# arm_project_files.net
KiCad netlist of a schematic drawn in EasyEDA Pro
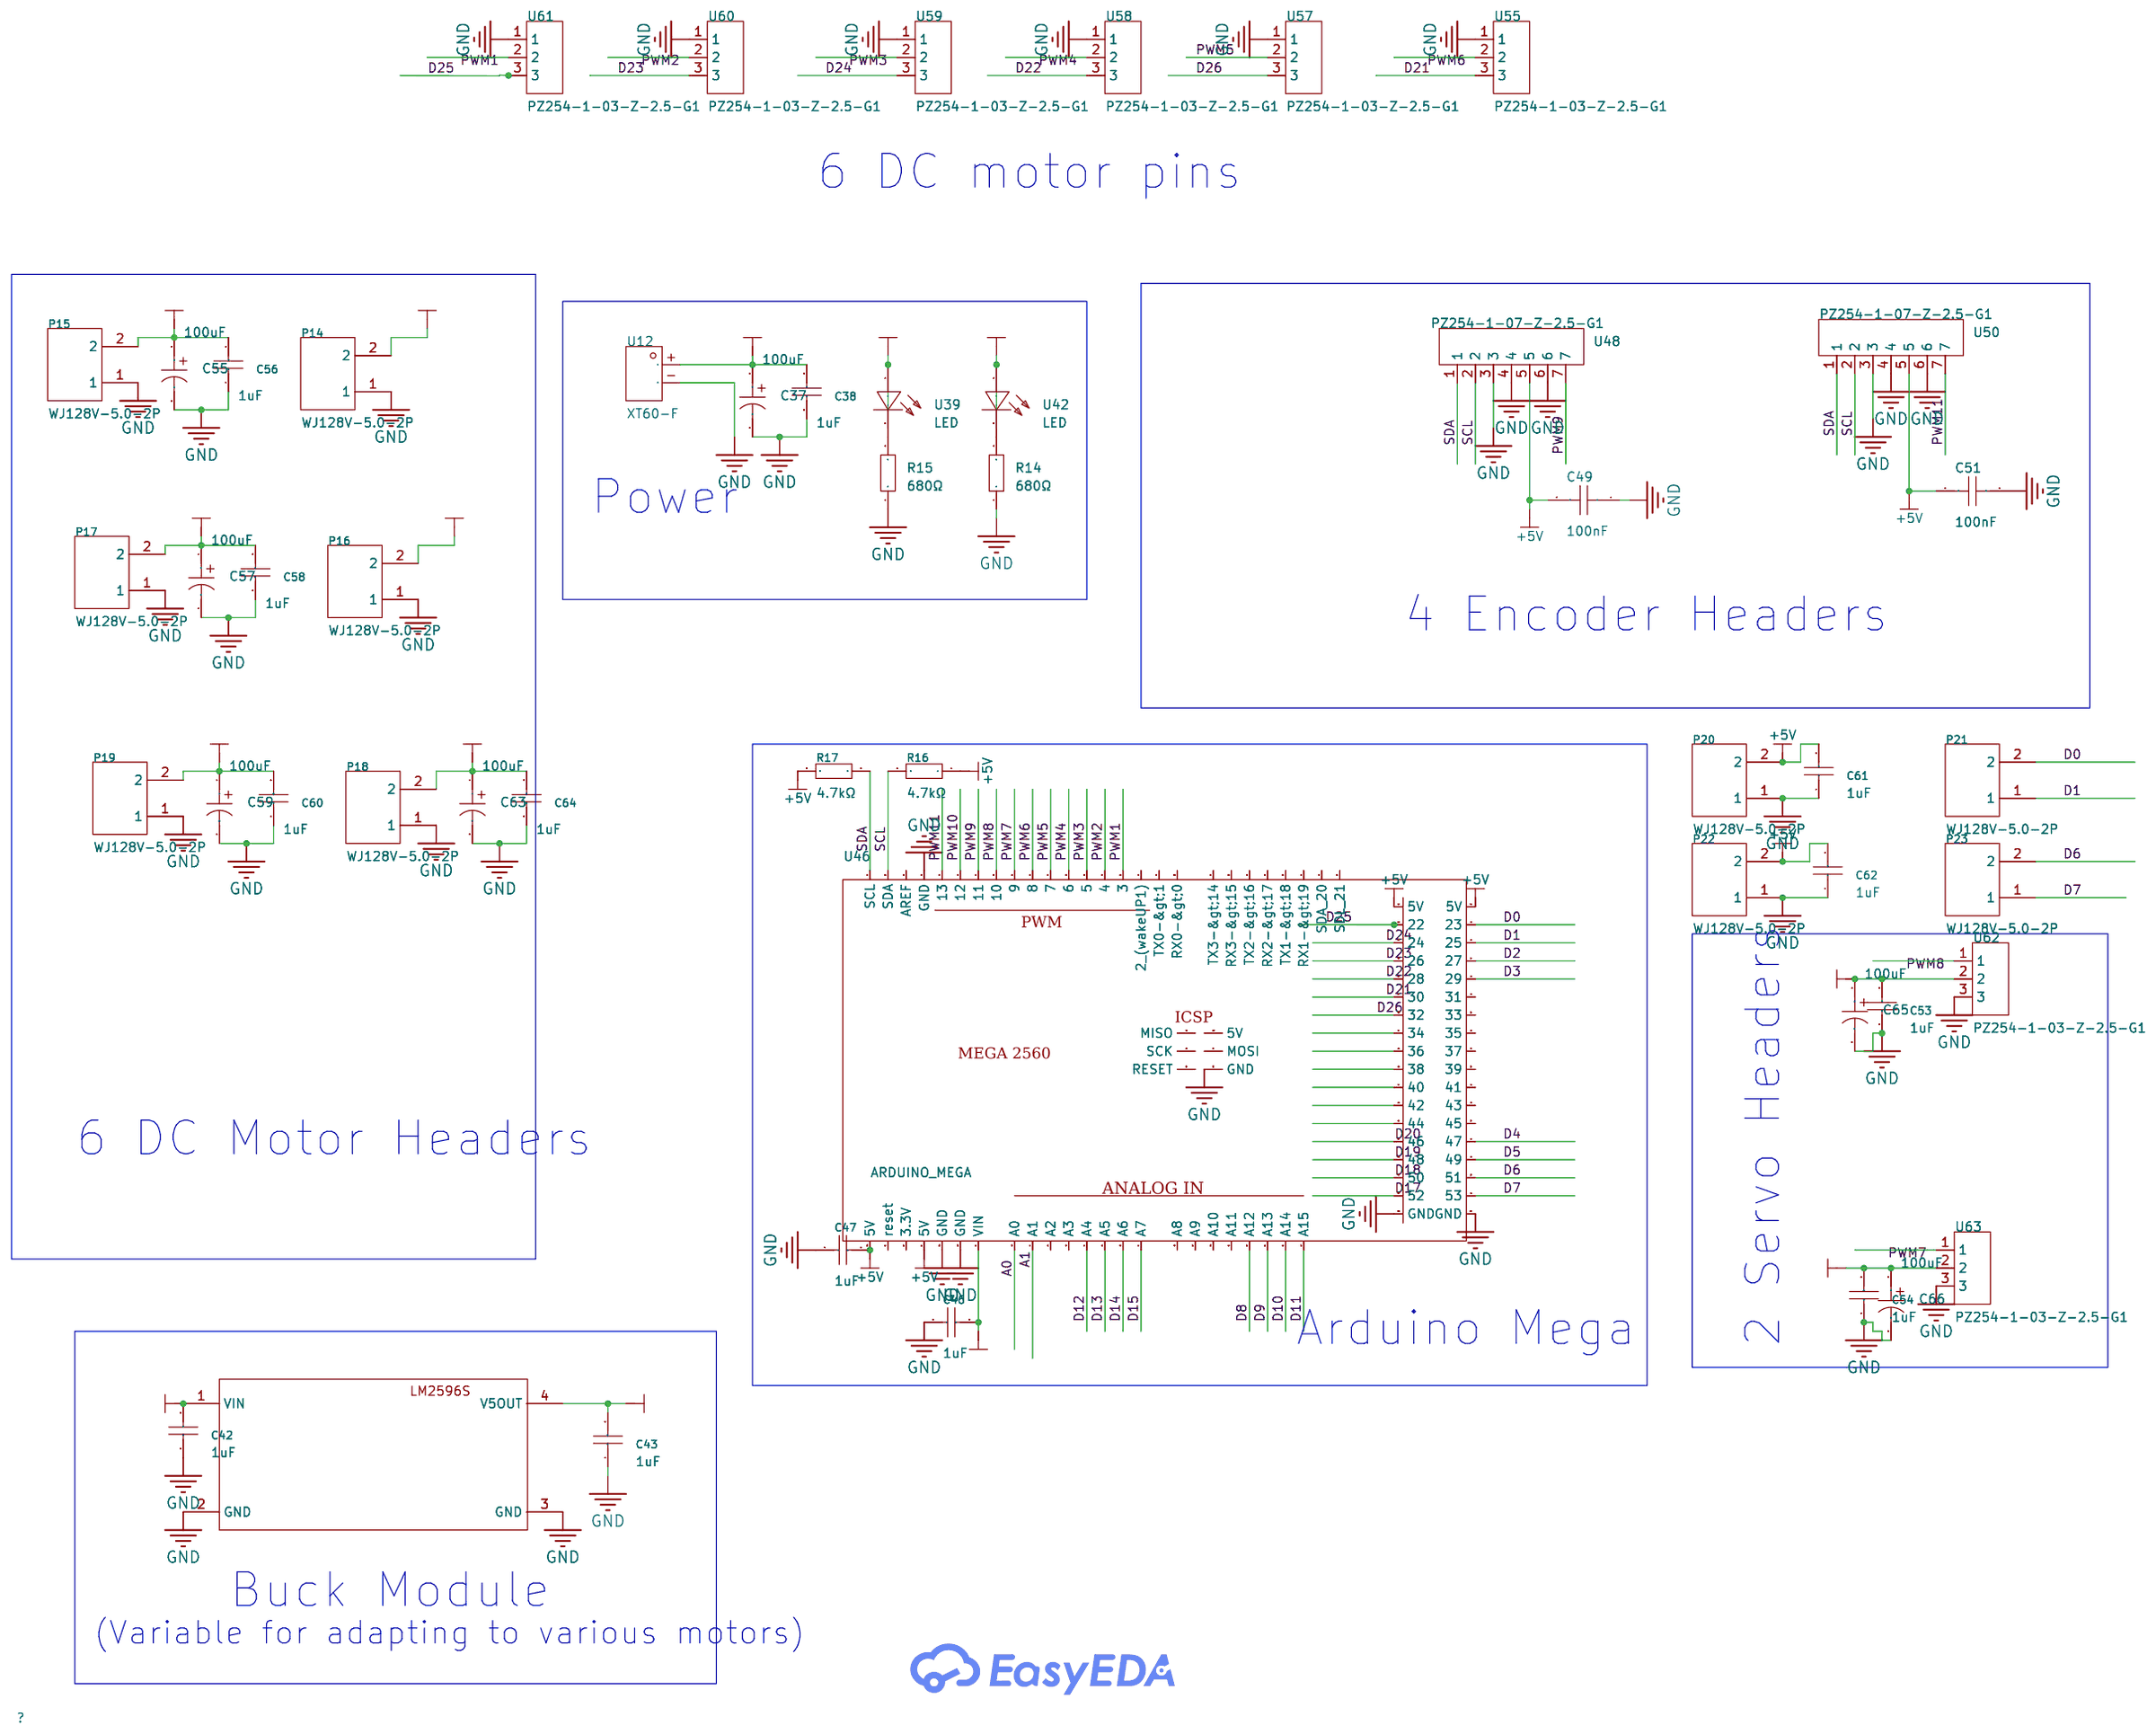
[diagram p0: schematic sheet]

(export (version "E")
  (design (tool "Eeschema 10.0.6"))
  (components
    (comp (ref "C37")
      (value "100uF")
      (footprint "easyedapro:CAP-TH_BD10.0-P5.00-D0.6-FD")
      (fields (field (name "Manufacturer Part") "100V100uF CD288") (field (name "Manufacturer") "HRK(鸿瑞凯电子)"))
      (libsource (lib "easyedapro") (part "100V100UF CD288"))
    )
    (comp (ref "C38")
      (value "1uF")
      (footprint "easyedapro:C0805")
      (fields
        (field (name "Manufacturer Part") "CC0805KKX7R8BB105")
        (field (name "Manufacturer") "YAGEO(国巨)")
      )
      (libsource (lib "easyedapro") (part "CC0805KKX7R8BB105"))
    )
    (comp (ref "C42")
      (value "1uF")
      (footprint "easyedapro:C0805")
      (fields
        (field (name "Manufacturer Part") "CC0805KKX7R8BB105")
        (field (name "Manufacturer") "YAGEO(国巨)")
      )
      (libsource (lib "easyedapro") (part "CC0805KKX7R8BB105"))
    )
    (comp (ref "C43")
      (value "1uF")
      (footprint "easyedapro:C0805")
      (fields
        (field (name "Manufacturer Part") "CC0805KKX7R8BB105")
        (field (name "Manufacturer") "YAGEO(国巨)")
      )
      (libsource (lib "easyedapro") (part "CC0805KKX7R8BB105"))
    )
    (comp (ref "C46")
      (value "1uF")
      (footprint "easyedapro:C0805")
      (fields
        (field (name "Manufacturer Part") "CC0805KKX7R8BB105")
        (field (name "Manufacturer") "YAGEO(国巨)")
      )
      (libsource (lib "easyedapro") (part "CC0805KKX7R8BB105"))
    )
    (comp (ref "C47")
      (value "1uF")
      (footprint "easyedapro:C0805")
      (fields
        (field (name "Manufacturer Part") "CC0805KKX7R8BB105")
        (field (name "Manufacturer") "YAGEO(国巨)")
      )
      (libsource (lib "easyedapro") (part "CC0805KKX7R8BB105"))
    )
    (comp (ref "C49")
      (value "100nF")
      (footprint "easyedapro:C0805")
      (description "Capacitance:100nF Tolerance:±10% Tolerance:±10% Voltage Rating:100V Temperature Coefficient:X7R")
      (fields (field (name "Manufacturer Part") "C0805X104K101T") (field (name "Manufacturer") "IHHEC(禾伸堂)"))
      (libsource (lib "easyedapro") (part "C0805X104K101T_C485772"))
    )
    (comp (ref "C51")
      (value "100nF")
      (footprint "easyedapro:C0805")
      (description "Capacitance:100nF Tolerance:±10% Tolerance:±10% Voltage Rating:100V Temperature Coefficient:X7R")
      (fields (field (name "Manufacturer Part") "C0805X104K101T") (field (name "Manufacturer") "IHHEC(禾伸堂)"))
      (libsource (lib "easyedapro") (part "C0805X104K101T_C485772"))
    )
    (comp (ref "C53")
      (value "1uF")
      (footprint "easyedapro:C0805")
      (fields
        (field (name "Manufacturer Part") "CC0805KKX7R8BB105")
        (field (name "Manufacturer") "YAGEO(国巨)")
      )
      (libsource (lib "easyedapro") (part "CC0805KKX7R8BB105"))
    )
    (comp (ref "C54")
      (value "1uF")
      (footprint "easyedapro:C0805")
      (fields
        (field (name "Manufacturer Part") "CC0805KKX7R8BB105")
        (field (name "Manufacturer") "YAGEO(国巨)")
      )
      (libsource (lib "easyedapro") (part "CC0805KKX7R8BB105"))
    )
    (comp (ref "C55")
      (value "100uF")
      (footprint "easyedapro:CAP-TH_BD10.0-P5.00-D0.6-FD")
      (fields (field (name "Manufacturer Part") "100V100uF CD288") (field (name "Manufacturer") "HRK(鸿瑞凯电子)"))
      (libsource (lib "easyedapro") (part "100V100UF CD288"))
    )
    (comp (ref "C56")
      (value "1uF")
      (footprint "easyedapro:C0805")
      (fields
        (field (name "Manufacturer Part") "CC0805KKX7R8BB105")
        (field (name "Manufacturer") "YAGEO(国巨)")
      )
      (libsource (lib "easyedapro") (part "CC0805KKX7R8BB105"))
    )
    (comp (ref "C57")
      (value "100uF")
      (footprint "easyedapro:CAP-TH_BD10.0-P5.00-D0.6-FD")
      (fields (field (name "Manufacturer Part") "100V100uF CD288") (field (name "Manufacturer") "HRK(鸿瑞凯电子)"))
      (libsource (lib "easyedapro") (part "100V100UF CD288"))
    )
    (comp (ref "C58")
      (value "1uF")
      (footprint "easyedapro:C0805")
      (fields
        (field (name "Manufacturer Part") "CC0805KKX7R8BB105")
        (field (name "Manufacturer") "YAGEO(国巨)")
      )
      (libsource (lib "easyedapro") (part "CC0805KKX7R8BB105"))
    )
    (comp (ref "C59")
      (value "100uF")
      (footprint "easyedapro:CAP-TH_BD10.0-P5.00-D0.6-FD")
      (fields (field (name "Manufacturer Part") "100V100uF CD288") (field (name "Manufacturer") "HRK(鸿瑞凯电子)"))
      (libsource (lib "easyedapro") (part "100V100UF CD288"))
    )
    (comp (ref "C60")
      (value "1uF")
      (footprint "easyedapro:C0805")
      (fields
        (field (name "Manufacturer Part") "CC0805KKX7R8BB105")
        (field (name "Manufacturer") "YAGEO(国巨)")
      )
      (libsource (lib "easyedapro") (part "CC0805KKX7R8BB105"))
    )
    (comp (ref "C61")
      (value "1uF")
      (footprint "easyedapro:C0805")
      (fields
        (field (name "Manufacturer Part") "CC0805KKX7R8BB105")
        (field (name "Manufacturer") "YAGEO(国巨)")
      )
      (libsource (lib "easyedapro") (part "CC0805KKX7R8BB105"))
    )
    (comp (ref "C62")
      (value "1uF")
      (footprint "easyedapro:C0805")
      (fields
        (field (name "Manufacturer Part") "CC0805KKX7R8BB105")
        (field (name "Manufacturer") "YAGEO(国巨)")
      )
      (libsource (lib "easyedapro") (part "CC0805KKX7R8BB105"))
    )
    (comp (ref "C63")
      (value "100uF")
      (footprint "easyedapro:CAP-TH_BD10.0-P5.00-D0.6-FD")
      (fields (field (name "Manufacturer Part") "100V100uF CD288") (field (name "Manufacturer") "HRK(鸿瑞凯电子)"))
      (libsource (lib "easyedapro") (part "100V100UF CD288"))
    )
    (comp (ref "C64")
      (value "1uF")
      (footprint "easyedapro:C0805")
      (fields
        (field (name "Manufacturer Part") "CC0805KKX7R8BB105")
        (field (name "Manufacturer") "YAGEO(国巨)")
      )
      (libsource (lib "easyedapro") (part "CC0805KKX7R8BB105"))
    )
    (comp (ref "C65")
      (value "100uF")
      (footprint "easyedapro:CAP-TH_BD10.0-P5.00-D0.6-FD")
      (fields (field (name "Manufacturer Part") "100V100uF CD288") (field (name "Manufacturer") "HRK(鸿瑞凯电子)"))
      (libsource (lib "easyedapro") (part "100V100UF CD288"))
    )
    (comp (ref "C66")
      (value "100uF")
      (footprint "easyedapro:CAP-TH_BD10.0-P5.00-D0.6-FD")
      (fields (field (name "Manufacturer Part") "100V100uF CD288") (field (name "Manufacturer") "HRK(鸿瑞凯电子)"))
      (libsource (lib "easyedapro") (part "100V100UF CD288"))
    )
    (comp (ref "P14")
      (value "WJ128V-5.0-2P")
      (footprint "easyedapro:CONN-TH_2P-P5.00_WJ128V-5.0-2P")
      (fields (field (name "Manufacturer") "KANGNEX(康奈克斯电气)"))
      (libsource (lib "easyedapro") (part "WJ128V-5.0-2P"))
    )
    (comp (ref "P15")
      (value "WJ128V-5.0-2P")
      (footprint "easyedapro:CONN-TH_2P-P5.00_WJ128V-5.0-2P")
      (fields (field (name "Manufacturer") "KANGNEX(康奈克斯电气)"))
      (libsource (lib "easyedapro") (part "WJ128V-5.0-2P"))
    )
    (comp (ref "P16")
      (value "WJ128V-5.0-2P")
      (footprint "easyedapro:CONN-TH_2P-P5.00_WJ128V-5.0-2P")
      (fields (field (name "Manufacturer") "KANGNEX(康奈克斯电气)"))
      (libsource (lib "easyedapro") (part "WJ128V-5.0-2P"))
    )
    (comp (ref "P17")
      (value "WJ128V-5.0-2P")
      (footprint "easyedapro:CONN-TH_2P-P5.00_WJ128V-5.0-2P")
      (fields (field (name "Manufacturer") "KANGNEX(康奈克斯电气)"))
      (libsource (lib "easyedapro") (part "WJ128V-5.0-2P"))
    )
    (comp (ref "P18")
      (value "WJ128V-5.0-2P")
      (footprint "easyedapro:CONN-TH_2P-P5.00_WJ128V-5.0-2P")
      (fields (field (name "Manufacturer") "KANGNEX(康奈克斯电气)"))
      (libsource (lib "easyedapro") (part "WJ128V-5.0-2P"))
    )
    (comp (ref "P19")
      (value "WJ128V-5.0-2P")
      (footprint "easyedapro:CONN-TH_2P-P5.00_WJ128V-5.0-2P")
      (fields (field (name "Manufacturer") "KANGNEX(康奈克斯电气)"))
      (libsource (lib "easyedapro") (part "WJ128V-5.0-2P"))
    )
    (comp (ref "P20")
      (value "WJ128V-5.0-2P")
      (footprint "easyedapro:CONN-TH_2P-P5.00_WJ128V-5.0-2P")
      (fields (field (name "Manufacturer") "KANGNEX(康奈克斯电气)"))
      (libsource (lib "easyedapro") (part "WJ128V-5.0-2P"))
    )
    (comp (ref "P21")
      (value "WJ128V-5.0-2P")
      (footprint "easyedapro:CONN-TH_2P-P5.00_WJ128V-5.0-2P")
      (fields (field (name "Manufacturer") "KANGNEX(康奈克斯电气)"))
      (libsource (lib "easyedapro") (part "WJ128V-5.0-2P"))
    )
    (comp (ref "P22")
      (value "WJ128V-5.0-2P")
      (footprint "easyedapro:CONN-TH_2P-P5.00_WJ128V-5.0-2P")
      (fields (field (name "Manufacturer") "KANGNEX(康奈克斯电气)"))
      (libsource (lib "easyedapro") (part "WJ128V-5.0-2P"))
    )
    (comp (ref "P23")
      (value "WJ128V-5.0-2P")
      (footprint "easyedapro:CONN-TH_2P-P5.00_WJ128V-5.0-2P")
      (fields (field (name "Manufacturer") "KANGNEX(康奈克斯电气)"))
      (libsource (lib "easyedapro") (part "WJ128V-5.0-2P"))
    )
    (comp (ref "R14")
      (value "680Ω")
      (footprint "easyedapro:R0805")
      (fields (field (name "Manufacturer Part") "CR0805F86800G") (field (name "Manufacturer") "LIZ(丽智电子)"))
      (libsource (lib "easyedapro") (part "CR0805F86800G"))
    )
    (comp (ref "R15")
      (value "680Ω")
      (footprint "easyedapro:R0805")
      (fields (field (name "Manufacturer Part") "CR0805F86800G") (field (name "Manufacturer") "LIZ(丽智电子)"))
      (libsource (lib "easyedapro") (part "CR0805F86800G"))
    )
    (comp (ref "R16")
      (value "4.7kΩ")
      (footprint "easyedapro:R1206")
      (fields (field (name "Manufacturer Part") "RMC12064.7K5%N") (field (name "Manufacturer") "Tyohm(幸亚电阻)"))
      (libsource (lib "easyedapro") (part "RMC12064.7K5%N"))
    )
    (comp (ref "R17")
      (value "4.7kΩ")
      (footprint "easyedapro:R1206")
      (fields (field (name "Manufacturer Part") "RMC12064.7K5%N") (field (name "Manufacturer") "Tyohm(幸亚电阻)"))
      (libsource (lib "easyedapro") (part "RMC12064.7K5%N"))
    )
    (comp (ref "U12")
      (value "XT60-F")
      (footprint "easyedapro:CONN-TH_XT60PB-F")
      (fields (field (name "Manufacturer") "AMASS(艾迈斯)"))
      (libsource (lib "easyedapro") (part "XT60-F"))
    )
    (comp (ref "U13")
      (value "776dda36e34043c08ff071d6b0b84ffa")
      (footprint "easyedapro:LM2596S_FP")
      (description "5V Buck converter")
      (libsource (lib "easyedapro") (part "LM2596S"))
    )
    (comp (ref "U39")
      (value "LED")
      (footprint "easyedapro:LED-TH_BD4.0-P2.54-FD_RED")
      (libsource (lib "easyedapro") (part "LED_C9900015665"))
    )
    (comp (ref "U42")
      (value "LED")
      (footprint "easyedapro:LED-TH_BD4.0-P2.54-FD_RED")
      (libsource (lib "easyedapro") (part "LED_C9900015665"))
    )
    (comp (ref "U46")
      (value "ARDUINO_MEGA")
      (footprint "easyedapro:ARDUINO_MEGA2560")
      (fields (field (name "Manufacturer Part") "ARDUINO MEGA"))
      (libsource (lib "easyedapro") (part "ARDUINO_MEGA"))
    )
    (comp (ref "U48")
      (value "PZ254-1-07-Z-2.5-G1")
      (footprint "easyedapro:HDR-TH_7P-P2.54-V-M")
      (fields (field (name "Manufacturer") "HCTL(华灿天禄)"))
      (libsource (lib "easyedapro") (part "PZ254-1-07-Z-2.5-G1"))
    )
    (comp (ref "U50")
      (value "PZ254-1-07-Z-2.5-G1")
      (footprint "easyedapro:HDR-TH_7P-P2.54-V-M")
      (fields (field (name "Manufacturer") "HCTL(华灿天禄)"))
      (libsource (lib "easyedapro") (part "PZ254-1-07-Z-2.5-G1"))
    )
    (comp (ref "U55")
      (value "PZ254-1-03-Z-2.5-G1")
      (footprint "easyedapro:HDR-TH_3P-P2.54-V-M")
      (fields (field (name "Manufacturer") "HCTL(华灿天禄)"))
      (libsource (lib "easyedapro") (part "PZ254-1-03-Z-2.5-G1"))
    )
    (comp (ref "U57")
      (value "PZ254-1-03-Z-2.5-G1")
      (footprint "easyedapro:HDR-TH_3P-P2.54-V-M")
      (fields (field (name "Manufacturer") "HCTL(华灿天禄)"))
      (libsource (lib "easyedapro") (part "PZ254-1-03-Z-2.5-G1"))
    )
    (comp (ref "U58")
      (value "PZ254-1-03-Z-2.5-G1")
      (footprint "easyedapro:HDR-TH_3P-P2.54-V-M")
      (fields (field (name "Manufacturer") "HCTL(华灿天禄)"))
      (libsource (lib "easyedapro") (part "PZ254-1-03-Z-2.5-G1"))
    )
    (comp (ref "U59")
      (value "PZ254-1-03-Z-2.5-G1")
      (footprint "easyedapro:HDR-TH_3P-P2.54-V-M")
      (fields (field (name "Manufacturer") "HCTL(华灿天禄)"))
      (libsource (lib "easyedapro") (part "PZ254-1-03-Z-2.5-G1"))
    )
    (comp (ref "U60")
      (value "PZ254-1-03-Z-2.5-G1")
      (footprint "easyedapro:HDR-TH_3P-P2.54-V-M")
      (fields (field (name "Manufacturer") "HCTL(华灿天禄)"))
      (libsource (lib "easyedapro") (part "PZ254-1-03-Z-2.5-G1"))
    )
    (comp (ref "U61")
      (value "PZ254-1-03-Z-2.5-G1")
      (footprint "easyedapro:HDR-TH_3P-P2.54-V-M")
      (fields (field (name "Manufacturer") "HCTL(华灿天禄)"))
      (libsource (lib "easyedapro") (part "PZ254-1-03-Z-2.5-G1"))
    )
    (comp (ref "U62")
      (value "PZ254-1-03-Z-2.5-G1")
      (footprint "easyedapro:HDR-TH_3P-P2.54-V-M")
      (fields (field (name "Manufacturer") "HCTL(华灿天禄)"))
      (libsource (lib "easyedapro") (part "PZ254-1-03-Z-2.5-G1"))
    )
    (comp (ref "U63")
      (value "PZ254-1-03-Z-2.5-G1")
      (footprint "easyedapro:HDR-TH_3P-P2.54-V-M")
      (fields (field (name "Manufacturer") "HCTL(华灿天禄)"))
      (libsource (lib "easyedapro") (part "PZ254-1-03-Z-2.5-G1"))
    )
  )
  (nets
    (net (code "1") (name "+5V") (class "Default")
      (node (ref "C47") (pin "2") (pinfunction "2_2") (pintype "input"))
      (node (ref "C49") (pin "2") (pinfunction "2_2") (pintype "unspecified"))
      (node (ref "C51") (pin "2") (pinfunction "2_2") (pintype "unspecified"))
      (node (ref "C61") (pin "2") (pinfunction "2_2") (pintype "input"))
      (node (ref "C62") (pin "2") (pinfunction "2_2") (pintype "input"))
      (node (ref "P20") (pin "2") (pinfunction "2_2") (pintype "input"))
      (node (ref "P22") (pin "2") (pinfunction "2_2") (pintype "input"))
      (node (ref "R16") (pin "1") (pinfunction "1_1") (pintype "input"))
      (node (ref "R17") (pin "2") (pinfunction "2_2") (pintype "input"))
      (node (ref "U46") (pin "5V") (pinfunction "5V_5V") (pintype "input"))
      (node (ref "U46") (pin "5V.") (pinfunction "5V_5V.") (pintype "input"))
      (node (ref "U46") (pin "5V..") (pinfunction "5V_5V..") (pintype "input"))
      (node (ref "U46") (pin "5V...") (pinfunction "5V_5V...") (pintype "input"))
      (node (ref "U48") (pin "5") (pinfunction "5_5") (pintype "unspecified"))
      (node (ref "U50") (pin "5") (pinfunction "5_5") (pintype "unspecified"))
    )
    (net (code "2") (name "+8V") (class "Default")
      (node (ref "C43") (pin "2") (pinfunction "2_2") (pintype "input"))
      (node (ref "C46") (pin "2") (pinfunction "2_2") (pintype "input"))
      (node (ref "C53") (pin "2") (pinfunction "2_2") (pintype "input"))
      (node (ref "C54") (pin "2") (pinfunction "2_2") (pintype "input"))
      (node (ref "C65") (pin "1") (pinfunction "1_1") (pintype "input"))
      (node (ref "C66") (pin "1") (pinfunction "1_1") (pintype "input"))
      (node (ref "U13") (pin "4") (pinfunction "V5OUT_4") (pintype "input"))
      (node (ref "U42") (pin "1") (pinfunction "+_1") (pintype "unspecified"))
      (node (ref "U46") (pin "VIN") (pinfunction "VIN_VIN") (pintype "input"))
      (node (ref "U62") (pin "2") (pinfunction "2_2") (pintype "unspecified"))
      (node (ref "U63") (pin "2") (pinfunction "2_2") (pintype "unspecified"))
    )
    (net (code "3") (name "/A0") (class "Default")
      (node (ref "U46") (pin "78") (pinfunction "A0_78") (pintype "input"))
    )
    (net (code "4") (name "/A1") (class "Default")
      (node (ref "U46") (pin "77") (pinfunction "A1_77") (pintype "input"))
    )
    (net (code "5") (name "/D0") (class "Default")
      (node (ref "P21") (pin "2") (pinfunction "2_2") (pintype "input"))
      (node (ref "U46") (pin "30") (pinfunction "23_30") (pintype "input"))
    )
    (net (code "6") (name "/D1") (class "Default")
      (node (ref "P21") (pin "1") (pinfunction "1_1") (pintype "input"))
      (node (ref "U46") (pin "32") (pinfunction "25_32") (pintype "input"))
    )
    (net (code "7") (name "/D2") (class "Default")
      (node (ref "U46") (pin "34") (pinfunction "27_34") (pintype "input"))
    )
    (net (code "8") (name "/D3") (class "Default")
      (node (ref "U46") (pin "36") (pinfunction "29_36") (pintype "input"))
    )
    (net (code "9") (name "/D4") (class "Default")
      (node (ref "U46") (pin "54") (pinfunction "47_54") (pintype "input"))
    )
    (net (code "10") (name "/D5") (class "Default")
      (node (ref "U46") (pin "56") (pinfunction "49_56") (pintype "input"))
    )
    (net (code "11") (name "/D6") (class "Default")
      (node (ref "P23") (pin "2") (pinfunction "2_2") (pintype "input"))
      (node (ref "U46") (pin "58") (pinfunction "51_58") (pintype "input"))
    )
    (net (code "12") (name "/D7") (class "Default")
      (node (ref "P23") (pin "1") (pinfunction "1_1") (pintype "input"))
      (node (ref "U46") (pin "60") (pinfunction "53_60") (pintype "input"))
    )
    (net (code "13") (name "/D8") (class "Default")
      (node (ref "U46") (pin "66") (pinfunction "A12_66") (pintype "input"))
    )
    (net (code "14") (name "/D9") (class "Default")
      (node (ref "U46") (pin "65") (pinfunction "A13_65") (pintype "input"))
    )
    (net (code "15") (name "/D10") (class "Default")
      (node (ref "U46") (pin "64") (pinfunction "A14_64") (pintype "input"))
    )
    (net (code "16") (name "/D11") (class "Default")
      (node (ref "U46") (pin "63") (pinfunction "A15_63") (pintype "input"))
    )
    (net (code "17") (name "/D12") (class "Default")
      (node (ref "U46") (pin "74") (pinfunction "A4_74") (pintype "input"))
    )
    (net (code "18") (name "/D13") (class "Default")
      (node (ref "U46") (pin "73") (pinfunction "A5_73") (pintype "input"))
    )
    (net (code "19") (name "/D14") (class "Default")
      (node (ref "U46") (pin "72") (pinfunction "A6_72") (pintype "input"))
    )
    (net (code "20") (name "/D15") (class "Default")
      (node (ref "U46") (pin "71") (pinfunction "A7_71") (pintype "input"))
    )
    (net (code "21") (name "/D17") (class "Default")
      (node (ref "U46") (pin "59") (pinfunction "52_59") (pintype "input"))
    )
    (net (code "22") (name "/D18") (class "Default")
      (node (ref "U46") (pin "57") (pinfunction "50_57") (pintype "input"))
    )
    (net (code "23") (name "/D19") (class "Default")
      (node (ref "U46") (pin "55") (pinfunction "48_55") (pintype "input"))
    )
    (net (code "24") (name "/D20") (class "Default")
      (node (ref "U46") (pin "53") (pinfunction "46_53") (pintype "input"))
    )
    (net (code "25") (name "/D21") (class "Default")
      (node (ref "U46") (pin "37") (pinfunction "30_37") (pintype "input"))
      (node (ref "U55") (pin "3") (pinfunction "3_3") (pintype "unspecified"))
    )
    (net (code "26") (name "/D22") (class "Default")
      (node (ref "U46") (pin "35") (pinfunction "28_35") (pintype "input"))
      (node (ref "U58") (pin "3") (pinfunction "3_3") (pintype "unspecified"))
    )
    (net (code "27") (name "/D23") (class "Default")
      (node (ref "U46") (pin "33") (pinfunction "26_33") (pintype "input"))
      (node (ref "U60") (pin "3") (pinfunction "3_3") (pintype "unspecified"))
    )
    (net (code "28") (name "/D24") (class "Default")
      (node (ref "U46") (pin "31") (pinfunction "24_31") (pintype "input"))
      (node (ref "U59") (pin "3") (pinfunction "3_3") (pintype "unspecified"))
    )
    (net (code "29") (name "/D25") (class "Default")
      (node (ref "U46") (pin "29") (pinfunction "22_29") (pintype "input"))
      (node (ref "U61") (pin "3") (pinfunction "3_3") (pintype "unspecified"))
    )
    (net (code "30") (name "/D26") (class "Default")
      (node (ref "U46") (pin "39") (pinfunction "32_39") (pintype "input"))
      (node (ref "U57") (pin "3") (pinfunction "3_3") (pintype "unspecified"))
    )
    (net (code "31") (name "/PWM1") (class "Default")
      (node (ref "U46") (pin "15") (pinfunction "3_15") (pintype "input"))
      (node (ref "U61") (pin "2") (pinfunction "2_2") (pintype "unspecified"))
    )
    (net (code "32") (name "/PWM2") (class "Default")
      (node (ref "U46") (pin "14") (pinfunction "4_14") (pintype "input"))
      (node (ref "U60") (pin "2") (pinfunction "2_2") (pintype "unspecified"))
    )
    (net (code "33") (name "/PWM3") (class "Default")
      (node (ref "U46") (pin "13") (pinfunction "5_13") (pintype "input"))
      (node (ref "U59") (pin "2") (pinfunction "2_2") (pintype "unspecified"))
    )
    (net (code "34") (name "/PWM4") (class "Default")
      (node (ref "U46") (pin "12") (pinfunction "6_12") (pintype "input"))
      (node (ref "U58") (pin "2") (pinfunction "2_2") (pintype "unspecified"))
    )
    (net (code "35") (name "/PWM5") (class "Default")
      (node (ref "U46") (pin "11") (pinfunction "7_11") (pintype "input"))
      (node (ref "U57") (pin "2") (pinfunction "2_2") (pintype "unspecified"))
    )
    (net (code "36") (name "/PWM6") (class "Default")
      (node (ref "U46") (pin "10") (pinfunction "8_10") (pintype "input"))
      (node (ref "U55") (pin "2") (pinfunction "2_2") (pintype "unspecified"))
    )
    (net (code "37") (name "/PWM7") (class "Default")
      (node (ref "U46") (pin "9") (pinfunction "9_9") (pintype "input"))
      (node (ref "U63") (pin "1") (pinfunction "1_1") (pintype "unspecified"))
    )
    (net (code "38") (name "/PWM8") (class "Default")
      (node (ref "U46") (pin "8") (pinfunction "10_8") (pintype "input"))
      (node (ref "U62") (pin "1") (pinfunction "1_1") (pintype "unspecified"))
    )
    (net (code "39") (name "/PWM9") (class "Default")
      (node (ref "U46") (pin "7") (pinfunction "11_7") (pintype "input"))
      (node (ref "U48") (pin "7") (pinfunction "7_7") (pintype "unspecified"))
    )
    (net (code "40") (name "/PWM10") (class "Default")
      (node (ref "U46") (pin "6") (pinfunction "12_6") (pintype "input"))
    )
    (net (code "41") (name "/PWM11") (class "Default")
      (node (ref "U46") (pin "5") (pinfunction "13_5") (pintype "input"))
      (node (ref "U50") (pin "7") (pinfunction "7_7") (pintype "unspecified"))
    )
    (net (code "42") (name "/SCL") (class "Default")
      (node (ref "R16") (pin "2") (pinfunction "2_2") (pintype "input"))
      (node (ref "U46") (pin "SDA") (pinfunction "SDA_SDA") (pintype "input"))
      (node (ref "U48") (pin "2") (pinfunction "2_2") (pintype "unspecified"))
      (node (ref "U50") (pin "2") (pinfunction "2_2") (pintype "unspecified"))
    )
    (net (code "43") (name "/SDA") (class "Default")
      (node (ref "R17") (pin "1") (pinfunction "1_1") (pintype "input"))
      (node (ref "U46") (pin "SCL") (pinfunction "SCL_SCL") (pintype "input"))
      (node (ref "U48") (pin "1") (pinfunction "1_1") (pintype "unspecified"))
      (node (ref "U50") (pin "1") (pinfunction "1_1") (pintype "unspecified"))
    )
    (net (code "44") (name "GND") (class "Default")
      (node (ref "C37") (pin "2") (pinfunction "2_2") (pintype "input"))
      (node (ref "C38") (pin "1") (pinfunction "1_1") (pintype "input"))
      (node (ref "C42") (pin "1") (pinfunction "1_1") (pintype "input"))
      (node (ref "C43") (pin "1") (pinfunction "1_1") (pintype "input"))
      (node (ref "C46") (pin "1") (pinfunction "1_1") (pintype "input"))
      (node (ref "C47") (pin "1") (pinfunction "1_1") (pintype "input"))
      (node (ref "C49") (pin "1") (pinfunction "1_1") (pintype "unspecified"))
      (node (ref "C51") (pin "1") (pinfunction "1_1") (pintype "unspecified"))
      (node (ref "C53") (pin "1") (pinfunction "1_1") (pintype "input"))
      (node (ref "C54") (pin "1") (pinfunction "1_1") (pintype "input"))
      (node (ref "C55") (pin "2") (pinfunction "2_2") (pintype "input"))
      (node (ref "C56") (pin "1") (pinfunction "1_1") (pintype "input"))
      (node (ref "C57") (pin "2") (pinfunction "2_2") (pintype "input"))
      (node (ref "C58") (pin "1") (pinfunction "1_1") (pintype "input"))
      (node (ref "C59") (pin "2") (pinfunction "2_2") (pintype "input"))
      (node (ref "C60") (pin "1") (pinfunction "1_1") (pintype "input"))
      (node (ref "C61") (pin "1") (pinfunction "1_1") (pintype "input"))
      (node (ref "C62") (pin "1") (pinfunction "1_1") (pintype "input"))
      (node (ref "C63") (pin "2") (pinfunction "2_2") (pintype "input"))
      (node (ref "C64") (pin "1") (pinfunction "1_1") (pintype "input"))
      (node (ref "C65") (pin "2") (pinfunction "2_2") (pintype "input"))
      (node (ref "C66") (pin "2") (pinfunction "2_2") (pintype "input"))
      (node (ref "P14") (pin "1") (pinfunction "1_1") (pintype "input"))
      (node (ref "P15") (pin "1") (pinfunction "1_1") (pintype "input"))
      (node (ref "P16") (pin "1") (pinfunction "1_1") (pintype "input"))
      (node (ref "P17") (pin "1") (pinfunction "1_1") (pintype "input"))
      (node (ref "P18") (pin "1") (pinfunction "1_1") (pintype "input"))
      (node (ref "P19") (pin "1") (pinfunction "1_1") (pintype "input"))
      (node (ref "P20") (pin "1") (pinfunction "1_1") (pintype "input"))
      (node (ref "P22") (pin "1") (pinfunction "1_1") (pintype "input"))
      (node (ref "R14") (pin "1") (pinfunction "1_1") (pintype "input"))
      (node (ref "R15") (pin "1") (pinfunction "1_1") (pintype "input"))
      (node (ref "U12") (pin "-") (pinfunction "2_-") (pintype "input"))
      (node (ref "U13") (pin "2") (pinfunction "GND_2") (pintype "input"))
      (node (ref "U13") (pin "3") (pinfunction "GND_3") (pintype "input"))
      (node (ref "U46") (pin "GND") (pinfunction "GND_GND") (pintype "input"))
      (node (ref "U48") (pin "3") (pinfunction "3_3") (pintype "unspecified"))
      (node (ref "U48") (pin "4") (pinfunction "4_4") (pintype "unspecified"))
      (node (ref "U48") (pin "6") (pinfunction "6_6") (pintype "unspecified"))
      (node (ref "U50") (pin "3") (pinfunction "3_3") (pintype "unspecified"))
      (node (ref "U50") (pin "4") (pinfunction "4_4") (pintype "unspecified"))
      (node (ref "U50") (pin "6") (pinfunction "6_6") (pintype "unspecified"))
      (node (ref "U55") (pin "1") (pinfunction "1_1") (pintype "unspecified"))
      (node (ref "U57") (pin "1") (pinfunction "1_1") (pintype "unspecified"))
      (node (ref "U58") (pin "1") (pinfunction "1_1") (pintype "unspecified"))
      (node (ref "U59") (pin "1") (pinfunction "1_1") (pintype "unspecified"))
      (node (ref "U60") (pin "1") (pinfunction "1_1") (pintype "unspecified"))
      (node (ref "U61") (pin "1") (pinfunction "1_1") (pintype "unspecified"))
      (node (ref "U62") (pin "3") (pinfunction "3_3") (pintype "unspecified"))
      (node (ref "U63") (pin "3") (pinfunction "3_3") (pintype "unspecified"))
    )
    (net (code "45") (name "Net-(U39--)") (class "Default")
      (node (ref "R15") (pin "2") (pinfunction "2_2") (pintype "input"))
      (node (ref "U39") (pin "2") (pinfunction "-_2") (pintype "unspecified"))
    )
    (net (code "46") (name "Net-(U42--)") (class "Default")
      (node (ref "R14") (pin "2") (pinfunction "2_2") (pintype "input"))
      (node (ref "U42") (pin "2") (pinfunction "-_2") (pintype "unspecified"))
    )
    (net (code "47") (name "VIN") (class "Default")
      (node (ref "C37") (pin "1") (pinfunction "1_1") (pintype "input"))
      (node (ref "C38") (pin "2") (pinfunction "2_2") (pintype "input"))
      (node (ref "C42") (pin "2") (pinfunction "2_2") (pintype "input"))
      (node (ref "C55") (pin "1") (pinfunction "1_1") (pintype "input"))
      (node (ref "C56") (pin "2") (pinfunction "2_2") (pintype "input"))
      (node (ref "C57") (pin "1") (pinfunction "1_1") (pintype "input"))
      (node (ref "C58") (pin "2") (pinfunction "2_2") (pintype "input"))
      (node (ref "C59") (pin "1") (pinfunction "1_1") (pintype "input"))
      (node (ref "C60") (pin "2") (pinfunction "2_2") (pintype "input"))
      (node (ref "C63") (pin "1") (pinfunction "1_1") (pintype "input"))
      (node (ref "C64") (pin "2") (pinfunction "2_2") (pintype "input"))
      (node (ref "P14") (pin "2") (pinfunction "2_2") (pintype "input"))
      (node (ref "P15") (pin "2") (pinfunction "2_2") (pintype "input"))
      (node (ref "P16") (pin "2") (pinfunction "2_2") (pintype "input"))
      (node (ref "P17") (pin "2") (pinfunction "2_2") (pintype "input"))
      (node (ref "P18") (pin "2") (pinfunction "2_2") (pintype "input"))
      (node (ref "P19") (pin "2") (pinfunction "2_2") (pintype "input"))
      (node (ref "U12") (pin "+") (pinfunction "1_+") (pintype "input"))
      (node (ref "U13") (pin "1") (pinfunction "VIN_1") (pintype "input"))
      (node (ref "U39") (pin "1") (pinfunction "+_1") (pintype "unspecified"))
    )
    (net (code "48") (name "unconnected-(U46-2_(wakeUP1)-Pad16)") (class "Default")
      (node (ref "U46") (pin "16") (pinfunction "2_(wakeUP1)_16") (pintype "input"))
    )
    (net (code "49") (name "unconnected-(U46-3.3V-Pad83)") (class "Default")
      (node (ref "U46") (pin "83") (pinfunction "3.3V_83") (pintype "input"))
    )
    (net (code "50") (name "unconnected-(U46-5V-Pad5VICSP)") (class "Default")
      (node (ref "U46") (pin "5VICSP") (pinfunction "5V_5VICSP") (pintype "input"))
    )
    (net (code "51") (name "unconnected-(U46-31-Pad38)") (class "Default")
      (node (ref "U46") (pin "38") (pinfunction "31_38") (pintype "input"))
    )
    (net (code "52") (name "unconnected-(U46-33-Pad40)") (class "Default")
      (node (ref "U46") (pin "40") (pinfunction "33_40") (pintype "input"))
    )
    (net (code "53") (name "unconnected-(U46-34-Pad41)") (class "Default")
      (node (ref "U46") (pin "41") (pinfunction "34_41") (pintype "input"))
    )
    (net (code "54") (name "unconnected-(U46-35-Pad42)") (class "Default")
      (node (ref "U46") (pin "42") (pinfunction "35_42") (pintype "input"))
    )
    (net (code "55") (name "unconnected-(U46-36-Pad43)") (class "Default")
      (node (ref "U46") (pin "43") (pinfunction "36_43") (pintype "input"))
    )
    (net (code "56") (name "unconnected-(U46-37-Pad44)") (class "Default")
      (node (ref "U46") (pin "44") (pinfunction "37_44") (pintype "input"))
    )
    (net (code "57") (name "unconnected-(U46-38-Pad45)") (class "Default")
      (node (ref "U46") (pin "45") (pinfunction "38_45") (pintype "input"))
    )
    (net (code "58") (name "unconnected-(U46-39-Pad46)") (class "Default")
      (node (ref "U46") (pin "46") (pinfunction "39_46") (pintype "input"))
    )
    (net (code "59") (name "unconnected-(U46-40-Pad47)") (class "Default")
      (node (ref "U46") (pin "47") (pinfunction "40_47") (pintype "input"))
    )
    (net (code "60") (name "unconnected-(U46-41-Pad48)") (class "Default")
      (node (ref "U46") (pin "48") (pinfunction "41_48") (pintype "input"))
    )
    (net (code "61") (name "unconnected-(U46-42-Pad49)") (class "Default")
      (node (ref "U46") (pin "49") (pinfunction "42_49") (pintype "input"))
    )
    (net (code "62") (name "unconnected-(U46-43-Pad50)") (class "Default")
      (node (ref "U46") (pin "50") (pinfunction "43_50") (pintype "input"))
    )
    (net (code "63") (name "unconnected-(U46-44-Pad51)") (class "Default")
      (node (ref "U46") (pin "51") (pinfunction "44_51") (pintype "input"))
    )
    (net (code "64") (name "unconnected-(U46-45-Pad52)") (class "Default")
      (node (ref "U46") (pin "52") (pinfunction "45_52") (pintype "input"))
    )
    (net (code "65") (name "unconnected-(U46-A2-Pad76)") (class "Default")
      (node (ref "U46") (pin "76") (pinfunction "A2_76") (pintype "input"))
    )
    (net (code "66") (name "unconnected-(U46-A3-Pad75)") (class "Default")
      (node (ref "U46") (pin "75") (pinfunction "A3_75") (pintype "input"))
    )
    (net (code "67") (name "unconnected-(U46-A8-Pad70)") (class "Default")
      (node (ref "U46") (pin "70") (pinfunction "A8_70") (pintype "input"))
    )
    (net (code "68") (name "unconnected-(U46-A9-Pad69)") (class "Default")
      (node (ref "U46") (pin "69") (pinfunction "A9_69") (pintype "input"))
    )
    (net (code "69") (name "unconnected-(U46-A10-Pad68)") (class "Default")
      (node (ref "U46") (pin "68") (pinfunction "A10_68") (pintype "input"))
    )
    (net (code "70") (name "unconnected-(U46-A11-Pad67)") (class "Default")
      (node (ref "U46") (pin "67") (pinfunction "A11_67") (pintype "input"))
    )
    (net (code "71") (name "unconnected-(U46-AREF-Pad3)") (class "Default")
      (node (ref "U46") (pin "3") (pinfunction "AREF_3") (pintype "input"))
    )
    (net (code "72") (name "unconnected-(U46-MISO-Pad86)") (class "Default")
      (node (ref "U46") (pin "86") (pinfunction "MISO_86") (pintype "input"))
    )
    (net (code "73") (name "unconnected-(U46-MOSI-Pad90)") (class "Default")
      (node (ref "U46") (pin "90") (pinfunction "MOSI_90") (pintype "input"))
    )
    (net (code "74") (name "unconnected-(U46-RESET-Pad88)") (class "Default")
      (node (ref "U46") (pin "88") (pinfunction "RESET_88") (pintype "input"))
    )
    (net (code "75") (name "unconnected-(U46-RX0-&gt;0-Pad18)") (class "Default")
      (node (ref "U46") (pin "18") (pinfunction "RX0-&gt;0_18") (pintype "input"))
    )
    (net (code "76") (name "unconnected-(U46-RX1-&gt;19-Pad24)") (class "Default")
      (node (ref "U46") (pin "24") (pinfunction "RX1-&gt;19_24") (pintype "input"))
    )
    (net (code "77") (name "unconnected-(U46-RX2-&gt;17-Pad22)") (class "Default")
      (node (ref "U46") (pin "22") (pinfunction "RX2-&gt;17_22") (pintype "input"))
    )
    (net (code "78") (name "unconnected-(U46-RX3-&gt;15-Pad20)") (class "Default")
      (node (ref "U46") (pin "20") (pinfunction "RX3-&gt;15_20") (pintype "input"))
    )
    (net (code "79") (name "unconnected-(U46-SCK-Pad87)") (class "Default")
      (node (ref "U46") (pin "87") (pinfunction "SCK_87") (pintype "input"))
    )
    (net (code "80") (name "unconnected-(U46-SDA_20-PadSDA2)") (class "Default")
      (node (ref "U46") (pin "SDA2") (pinfunction "SDA_20_SDA2") (pintype "input"))
    )
    (net (code "81") (name "unconnected-(U46-SDL_21-PadSCL2)") (class "Default")
      (node (ref "U46") (pin "SCL2") (pinfunction "SDL_21_SCL2") (pintype "input"))
    )
    (net (code "82") (name "unconnected-(U46-TX0-&gt;1-Pad17)") (class "Default")
      (node (ref "U46") (pin "17") (pinfunction "TX0-&gt;1_17") (pintype "input"))
    )
    (net (code "83") (name "unconnected-(U46-TX1-&gt;18-Pad23)") (class "Default")
      (node (ref "U46") (pin "23") (pinfunction "TX1-&gt;18_23") (pintype "input"))
    )
    (net (code "84") (name "unconnected-(U46-TX2-&gt;16-Pad21)") (class "Default")
      (node (ref "U46") (pin "21") (pinfunction "TX2-&gt;16_21") (pintype "input"))
    )
    (net (code "85") (name "unconnected-(U46-TX3-&gt;14-Pad19)") (class "Default")
      (node (ref "U46") (pin "19") (pinfunction "TX3-&gt;14_19") (pintype "input"))
    )
    (net (code "86") (name "unconnected-(U46-reset-Pad84)") (class "Default")
      (node (ref "U46") (pin "84") (pinfunction "reset_84") (pintype "input"))
    )
  )
)
